# INTERFACE.net
KiCad netlist of a schematic drawn in Altium Designer
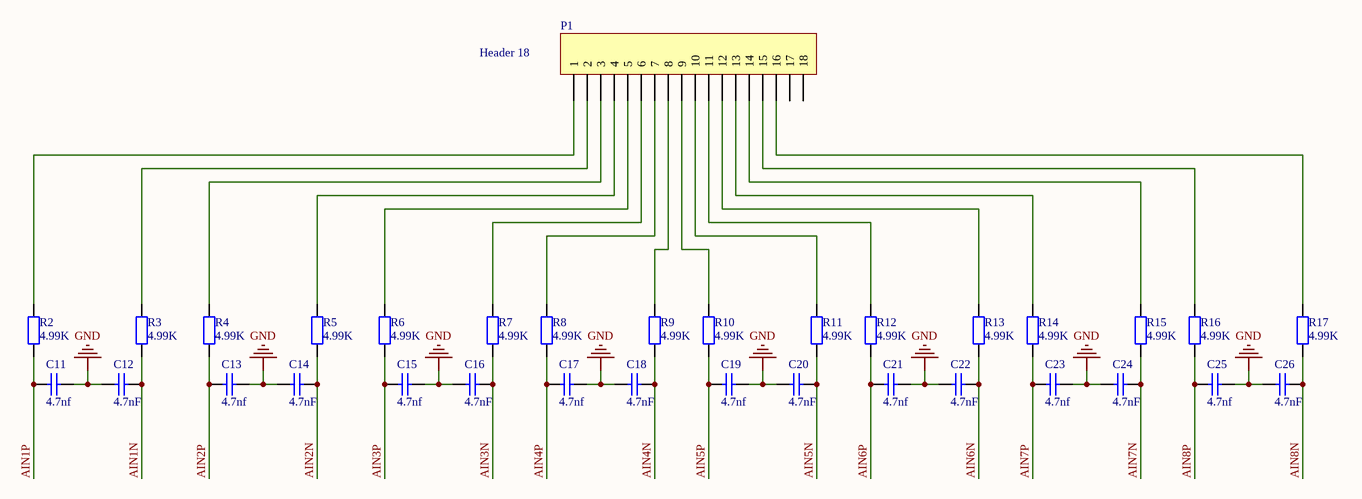
[diagram p0: INTERFACE.SchDoc]

(export (version "E")
  (design (tool "Eeschema 10.0.6"))
  (components
    (comp (ref "C11")
      (value "4.7nf")
      (footprint "CAP-C0603-H0.9mm")
      (description "CER 10UF 25V X8R 1210")
      (fields (field (name "DIGIKEY PART NUMBER") "478-1244-1-ND"))
      (libsource (lib "LibSch") (part "C0603"))
    )
    (comp (ref "C12")
      (value "4.7nF")
      (footprint "CAP-C0603-H0.9mm")
      (description "CER 10UF 25V X8R 1210")
      (fields (field (name "DIGIKEY PART NUMBER") "478-1244-1-ND"))
      (libsource (lib "LibSch") (part "C0603"))
    )
    (comp (ref "C13")
      (value "4.7nf")
      (footprint "CAP-C0603-H0.9mm")
      (description "CER 10UF 25V X8R 1210")
      (fields (field (name "DIGIKEY PART NUMBER") "478-1244-1-ND"))
      (libsource (lib "LibSch") (part "C0603"))
    )
    (comp (ref "C14")
      (value "4.7nF")
      (footprint "CAP-C0603-H0.9mm")
      (description "CER 10UF 25V X8R 1210")
      (fields (field (name "DIGIKEY PART NUMBER") "478-1244-1-ND"))
      (libsource (lib "LibSch") (part "C0603"))
    )
    (comp (ref "C15")
      (value "4.7nf")
      (footprint "CAP-C0603-H0.9mm")
      (description "CER 10UF 25V X8R 1210")
      (fields (field (name "DIGIKEY PART NUMBER") "478-1244-1-ND"))
      (libsource (lib "LibSch") (part "C0603"))
    )
    (comp (ref "C16")
      (value "4.7nF")
      (footprint "CAP-C0603-H0.9mm")
      (description "CER 10UF 25V X8R 1210")
      (fields (field (name "DIGIKEY PART NUMBER") "478-1244-1-ND"))
      (libsource (lib "LibSch") (part "C0603"))
    )
    (comp (ref "C17")
      (value "4.7nf")
      (footprint "CAP-C0603-H0.9mm")
      (description "CER 10UF 25V X8R 1210")
      (fields (field (name "DIGIKEY PART NUMBER") "478-1244-1-ND"))
      (libsource (lib "LibSch") (part "C0603"))
    )
    (comp (ref "C18")
      (value "4.7nF")
      (footprint "CAP-C0603-H0.9mm")
      (description "CER 10UF 25V X8R 1210")
      (fields (field (name "DIGIKEY PART NUMBER") "478-1244-1-ND"))
      (libsource (lib "LibSch") (part "C0603"))
    )
    (comp (ref "C19")
      (value "4.7nf")
      (footprint "CAP-C0603-H0.9mm")
      (description "CER 10UF 25V X8R 1210")
      (fields (field (name "DIGIKEY PART NUMBER") "478-1244-1-ND"))
      (libsource (lib "LibSch") (part "C0603"))
    )
    (comp (ref "C20")
      (value "4.7nF")
      (footprint "CAP-C0603-H0.9mm")
      (description "CER 10UF 25V X8R 1210")
      (fields (field (name "DIGIKEY PART NUMBER") "478-1244-1-ND"))
      (libsource (lib "LibSch") (part "C0603"))
    )
    (comp (ref "C21")
      (value "4.7nf")
      (footprint "CAP-C0603-H0.9mm")
      (description "CER 10UF 25V X8R 1210")
      (fields (field (name "DIGIKEY PART NUMBER") "478-1244-1-ND"))
      (libsource (lib "LibSch") (part "C0603"))
    )
    (comp (ref "C22")
      (value "4.7nF")
      (footprint "CAP-C0603-H0.9mm")
      (description "CER 10UF 25V X8R 1210")
      (fields (field (name "DIGIKEY PART NUMBER") "478-1244-1-ND"))
      (libsource (lib "LibSch") (part "C0603"))
    )
    (comp (ref "C23")
      (value "4.7nf")
      (footprint "CAP-C0603-H0.9mm")
      (description "CER 10UF 25V X8R 1210")
      (fields (field (name "DIGIKEY PART NUMBER") "478-1244-1-ND"))
      (libsource (lib "LibSch") (part "C0603"))
    )
    (comp (ref "C24")
      (value "4.7nF")
      (footprint "CAP-C0603-H0.9mm")
      (description "CER 10UF 25V X8R 1210")
      (fields (field (name "DIGIKEY PART NUMBER") "478-1244-1-ND"))
      (libsource (lib "LibSch") (part "C0603"))
    )
    (comp (ref "C25")
      (value "4.7nf")
      (footprint "CAP-C0603-H0.9mm")
      (description "CER 10UF 25V X8R 1210")
      (fields (field (name "DIGIKEY PART NUMBER") "478-1244-1-ND"))
      (libsource (lib "LibSch") (part "C0603"))
    )
    (comp (ref "C26")
      (value "4.7nF")
      (footprint "CAP-C0603-H0.9mm")
      (description "CER 10UF 25V X8R 1210")
      (fields (field (name "DIGIKEY PART NUMBER") "478-1244-1-ND"))
      (libsource (lib "LibSch") (part "C0603"))
    )
    (comp (ref "P1")
      (value "Header 18")
      (footprint "HDR1X18")
      (description "Header, 18-Pin")
      (fields (field (name "PUBLISHER") "Altium Limited"))
      (libsource (lib "Miscellaneous Connectors") (part "Header 18"))
    )
    (comp (ref "R2")
      (value "4.99K")
      (footprint "RES-0805-H0.6mm")
      (description "RES SMD 33 OHM 1% 1/10W 0603")
      (libsource (lib "LibSch") (part "R"))
    )
    (comp (ref "R3")
      (value "4.99K")
      (footprint "RES-0805-H0.6mm")
      (description "RES SMD 33 OHM 1% 1/10W 0603")
      (libsource (lib "LibSch") (part "R"))
    )
    (comp (ref "R4")
      (value "4.99K")
      (footprint "RES-0805-H0.6mm")
      (description "RES SMD 33 OHM 1% 1/10W 0603")
      (libsource (lib "LibSch") (part "R"))
    )
    (comp (ref "R5")
      (value "4.99K")
      (footprint "RES-0805-H0.6mm")
      (description "RES SMD 33 OHM 1% 1/10W 0603")
      (libsource (lib "LibSch") (part "R"))
    )
    (comp (ref "R6")
      (value "4.99K")
      (footprint "RES-0805-H0.6mm")
      (description "RES SMD 33 OHM 1% 1/10W 0603")
      (libsource (lib "LibSch") (part "R"))
    )
    (comp (ref "R7")
      (value "4.99K")
      (footprint "RES-0805-H0.6mm")
      (description "RES SMD 33 OHM 1% 1/10W 0603")
      (libsource (lib "LibSch") (part "R"))
    )
    (comp (ref "R8")
      (value "4.99K")
      (footprint "RES-0805-H0.6mm")
      (description "RES SMD 33 OHM 1% 1/10W 0603")
      (libsource (lib "LibSch") (part "R"))
    )
    (comp (ref "R9")
      (value "4.99K")
      (footprint "RES-0805-H0.6mm")
      (description "RES SMD 33 OHM 1% 1/10W 0603")
      (libsource (lib "LibSch") (part "R"))
    )
    (comp (ref "R10")
      (value "4.99K")
      (footprint "RES-0805-H0.6mm")
      (description "RES SMD 33 OHM 1% 1/10W 0603")
      (libsource (lib "LibSch") (part "R"))
    )
    (comp (ref "R11")
      (value "4.99K")
      (footprint "RES-0805-H0.6mm")
      (description "RES SMD 33 OHM 1% 1/10W 0603")
      (libsource (lib "LibSch") (part "R"))
    )
    (comp (ref "R12")
      (value "4.99K")
      (footprint "RES-0805-H0.6mm")
      (description "RES SMD 33 OHM 1% 1/10W 0603")
      (libsource (lib "LibSch") (part "R"))
    )
    (comp (ref "R13")
      (value "4.99K")
      (footprint "RES-0805-H0.6mm")
      (description "RES SMD 33 OHM 1% 1/10W 0603")
      (libsource (lib "LibSch") (part "R"))
    )
    (comp (ref "R14")
      (value "4.99K")
      (footprint "RES-0805-H0.6mm")
      (description "RES SMD 33 OHM 1% 1/10W 0603")
      (libsource (lib "LibSch") (part "R"))
    )
    (comp (ref "R15")
      (value "4.99K")
      (footprint "RES-0805-H0.6mm")
      (description "RES SMD 33 OHM 1% 1/10W 0603")
      (libsource (lib "LibSch") (part "R"))
    )
    (comp (ref "R16")
      (value "4.99K")
      (footprint "RES-0805-H0.6mm")
      (description "RES SMD 33 OHM 1% 1/10W 0603")
      (libsource (lib "LibSch") (part "R"))
    )
    (comp (ref "R17")
      (value "4.99K")
      (footprint "RES-0805-H0.6mm")
      (description "RES SMD 33 OHM 1% 1/10W 0603")
      (libsource (lib "LibSch") (part "R"))
    )
  )
  (nets
    (net (code "1") (name "/AIN1N") (class "Default")
      (node (ref "C12") (pin "1") (pinfunction "1_1") (pintype "passive"))
      (node (ref "R3") (pin "1") (pinfunction "1_1") (pintype "passive"))
    )
    (net (code "2") (name "/AIN1P") (class "Default")
      (node (ref "C11") (pin "2") (pinfunction "2_2") (pintype "passive"))
      (node (ref "R2") (pin "1") (pinfunction "1_1") (pintype "passive"))
    )
    (net (code "3") (name "/AIN2N") (class "Default")
      (node (ref "C14") (pin "1") (pinfunction "1_1") (pintype "passive"))
      (node (ref "R5") (pin "1") (pinfunction "1_1") (pintype "passive"))
    )
    (net (code "4") (name "/AIN2P") (class "Default")
      (node (ref "C13") (pin "2") (pinfunction "2_2") (pintype "passive"))
      (node (ref "R4") (pin "1") (pinfunction "1_1") (pintype "passive"))
    )
    (net (code "5") (name "/AIN3N") (class "Default")
      (node (ref "C16") (pin "1") (pinfunction "1_1") (pintype "passive"))
      (node (ref "R7") (pin "1") (pinfunction "1_1") (pintype "passive"))
    )
    (net (code "6") (name "/AIN3P") (class "Default")
      (node (ref "C15") (pin "2") (pinfunction "2_2") (pintype "passive"))
      (node (ref "R6") (pin "1") (pinfunction "1_1") (pintype "passive"))
    )
    (net (code "7") (name "/AIN4N") (class "Default")
      (node (ref "C18") (pin "1") (pinfunction "1_1") (pintype "passive"))
      (node (ref "R9") (pin "1") (pinfunction "1_1") (pintype "passive"))
    )
    (net (code "8") (name "/AIN4P") (class "Default")
      (node (ref "C17") (pin "2") (pinfunction "2_2") (pintype "passive"))
      (node (ref "R8") (pin "1") (pinfunction "1_1") (pintype "passive"))
    )
    (net (code "9") (name "/AIN5N") (class "Default")
      (node (ref "C20") (pin "1") (pinfunction "1_1") (pintype "passive"))
      (node (ref "R11") (pin "1") (pinfunction "1_1") (pintype "passive"))
    )
    (net (code "10") (name "/AIN5P") (class "Default")
      (node (ref "C19") (pin "2") (pinfunction "2_2") (pintype "passive"))
      (node (ref "R10") (pin "1") (pinfunction "1_1") (pintype "passive"))
    )
    (net (code "11") (name "/AIN6N") (class "Default")
      (node (ref "C22") (pin "1") (pinfunction "1_1") (pintype "passive"))
      (node (ref "R13") (pin "1") (pinfunction "1_1") (pintype "passive"))
    )
    (net (code "12") (name "/AIN6P") (class "Default")
      (node (ref "C21") (pin "2") (pinfunction "2_2") (pintype "passive"))
      (node (ref "R12") (pin "1") (pinfunction "1_1") (pintype "passive"))
    )
    (net (code "13") (name "/AIN7N") (class "Default")
      (node (ref "C24") (pin "1") (pinfunction "1_1") (pintype "passive"))
      (node (ref "R15") (pin "1") (pinfunction "1_1") (pintype "passive"))
    )
    (net (code "14") (name "/AIN7P") (class "Default")
      (node (ref "C23") (pin "2") (pinfunction "2_2") (pintype "passive"))
      (node (ref "R14") (pin "1") (pinfunction "1_1") (pintype "passive"))
    )
    (net (code "15") (name "/AIN8N") (class "Default")
      (node (ref "C26") (pin "1") (pinfunction "1_1") (pintype "passive"))
      (node (ref "R17") (pin "1") (pinfunction "1_1") (pintype "passive"))
    )
    (net (code "16") (name "/AIN8P") (class "Default")
      (node (ref "C25") (pin "2") (pinfunction "2_2") (pintype "passive"))
      (node (ref "R16") (pin "1") (pinfunction "1_1") (pintype "passive"))
    )
    (net (code "17") (name "GND") (class "Default")
      (node (ref "C11") (pin "1") (pinfunction "1_1") (pintype "passive"))
      (node (ref "C12") (pin "2") (pinfunction "2_2") (pintype "passive"))
      (node (ref "C13") (pin "1") (pinfunction "1_1") (pintype "passive"))
      (node (ref "C14") (pin "2") (pinfunction "2_2") (pintype "passive"))
      (node (ref "C15") (pin "1") (pinfunction "1_1") (pintype "passive"))
      (node (ref "C16") (pin "2") (pinfunction "2_2") (pintype "passive"))
      (node (ref "C17") (pin "1") (pinfunction "1_1") (pintype "passive"))
      (node (ref "C18") (pin "2") (pinfunction "2_2") (pintype "passive"))
      (node (ref "C19") (pin "1") (pinfunction "1_1") (pintype "passive"))
      (node (ref "C20") (pin "2") (pinfunction "2_2") (pintype "passive"))
      (node (ref "C21") (pin "1") (pinfunction "1_1") (pintype "passive"))
      (node (ref "C22") (pin "2") (pinfunction "2_2") (pintype "passive"))
      (node (ref "C23") (pin "1") (pinfunction "1_1") (pintype "passive"))
      (node (ref "C24") (pin "2") (pinfunction "2_2") (pintype "passive"))
      (node (ref "C25") (pin "1") (pinfunction "1_1") (pintype "passive"))
      (node (ref "C26") (pin "2") (pinfunction "2_2") (pintype "passive"))
    )
    (net (code "18") (name "Net-(P1-Pad1)") (class "Default")
      (node (ref "P1") (pin "1") (pinfunction "1_1") (pintype "passive"))
      (node (ref "R2") (pin "2") (pinfunction "2_2") (pintype "passive"))
    )
    (net (code "19") (name "Net-(P1-Pad2)") (class "Default")
      (node (ref "P1") (pin "2") (pinfunction "2_2") (pintype "passive"))
      (node (ref "R3") (pin "2") (pinfunction "2_2") (pintype "passive"))
    )
    (net (code "20") (name "Net-(P1-Pad3)") (class "Default")
      (node (ref "P1") (pin "3") (pinfunction "3_3") (pintype "passive"))
      (node (ref "R4") (pin "2") (pinfunction "2_2") (pintype "passive"))
    )
    (net (code "21") (name "Net-(P1-Pad4)") (class "Default")
      (node (ref "P1") (pin "4") (pinfunction "4_4") (pintype "passive"))
      (node (ref "R5") (pin "2") (pinfunction "2_2") (pintype "passive"))
    )
    (net (code "22") (name "Net-(P1-Pad5)") (class "Default")
      (node (ref "P1") (pin "5") (pinfunction "5_5") (pintype "passive"))
      (node (ref "R6") (pin "2") (pinfunction "2_2") (pintype "passive"))
    )
    (net (code "23") (name "Net-(P1-Pad6)") (class "Default")
      (node (ref "P1") (pin "6") (pinfunction "6_6") (pintype "passive"))
      (node (ref "R7") (pin "2") (pinfunction "2_2") (pintype "passive"))
    )
    (net (code "24") (name "Net-(P1-Pad7)") (class "Default")
      (node (ref "P1") (pin "7") (pinfunction "7_7") (pintype "passive"))
      (node (ref "R8") (pin "2") (pinfunction "2_2") (pintype "passive"))
    )
    (net (code "25") (name "Net-(P1-Pad8)") (class "Default")
      (node (ref "P1") (pin "8") (pinfunction "8_8") (pintype "passive"))
      (node (ref "R9") (pin "2") (pinfunction "2_2") (pintype "passive"))
    )
    (net (code "26") (name "Net-(P1-Pad9)") (class "Default")
      (node (ref "P1") (pin "9") (pinfunction "9_9") (pintype "passive"))
      (node (ref "R10") (pin "2") (pinfunction "2_2") (pintype "passive"))
    )
    (net (code "27") (name "Net-(P1-Pad10)") (class "Default")
      (node (ref "P1") (pin "10") (pinfunction "10_10") (pintype "passive"))
      (node (ref "R11") (pin "2") (pinfunction "2_2") (pintype "passive"))
    )
    (net (code "28") (name "Net-(P1-Pad11)") (class "Default")
      (node (ref "P1") (pin "11") (pinfunction "11_11") (pintype "passive"))
      (node (ref "R12") (pin "2") (pinfunction "2_2") (pintype "passive"))
    )
    (net (code "29") (name "Net-(P1-Pad12)") (class "Default")
      (node (ref "P1") (pin "12") (pinfunction "12_12") (pintype "passive"))
      (node (ref "R13") (pin "2") (pinfunction "2_2") (pintype "passive"))
    )
    (net (code "30") (name "Net-(P1-Pad13)") (class "Default")
      (node (ref "P1") (pin "13") (pinfunction "13_13") (pintype "passive"))
      (node (ref "R14") (pin "2") (pinfunction "2_2") (pintype "passive"))
    )
    (net (code "31") (name "Net-(P1-Pad14)") (class "Default")
      (node (ref "P1") (pin "14") (pinfunction "14_14") (pintype "passive"))
      (node (ref "R15") (pin "2") (pinfunction "2_2") (pintype "passive"))
    )
    (net (code "32") (name "Net-(P1-Pad15)") (class "Default")
      (node (ref "P1") (pin "15") (pinfunction "15_15") (pintype "passive"))
      (node (ref "R16") (pin "2") (pinfunction "2_2") (pintype "passive"))
    )
    (net (code "33") (name "Net-(P1-Pad16)") (class "Default")
      (node (ref "P1") (pin "16") (pinfunction "16_16") (pintype "passive"))
      (node (ref "R17") (pin "2") (pinfunction "2_2") (pintype "passive"))
    )
    (net (code "34") (name "unconnected-(P1-Pad17)") (class "Default")
      (node (ref "P1") (pin "17") (pinfunction "17_17") (pintype "passive"))
    )
    (net (code "35") (name "unconnected-(P1-Pad18)") (class "Default")
      (node (ref "P1") (pin "18") (pinfunction "18_18") (pintype "passive"))
    )
  )
)
